# 40_PP1_PWR.net
KiCad netlist of a schematic drawn in Altium Designer
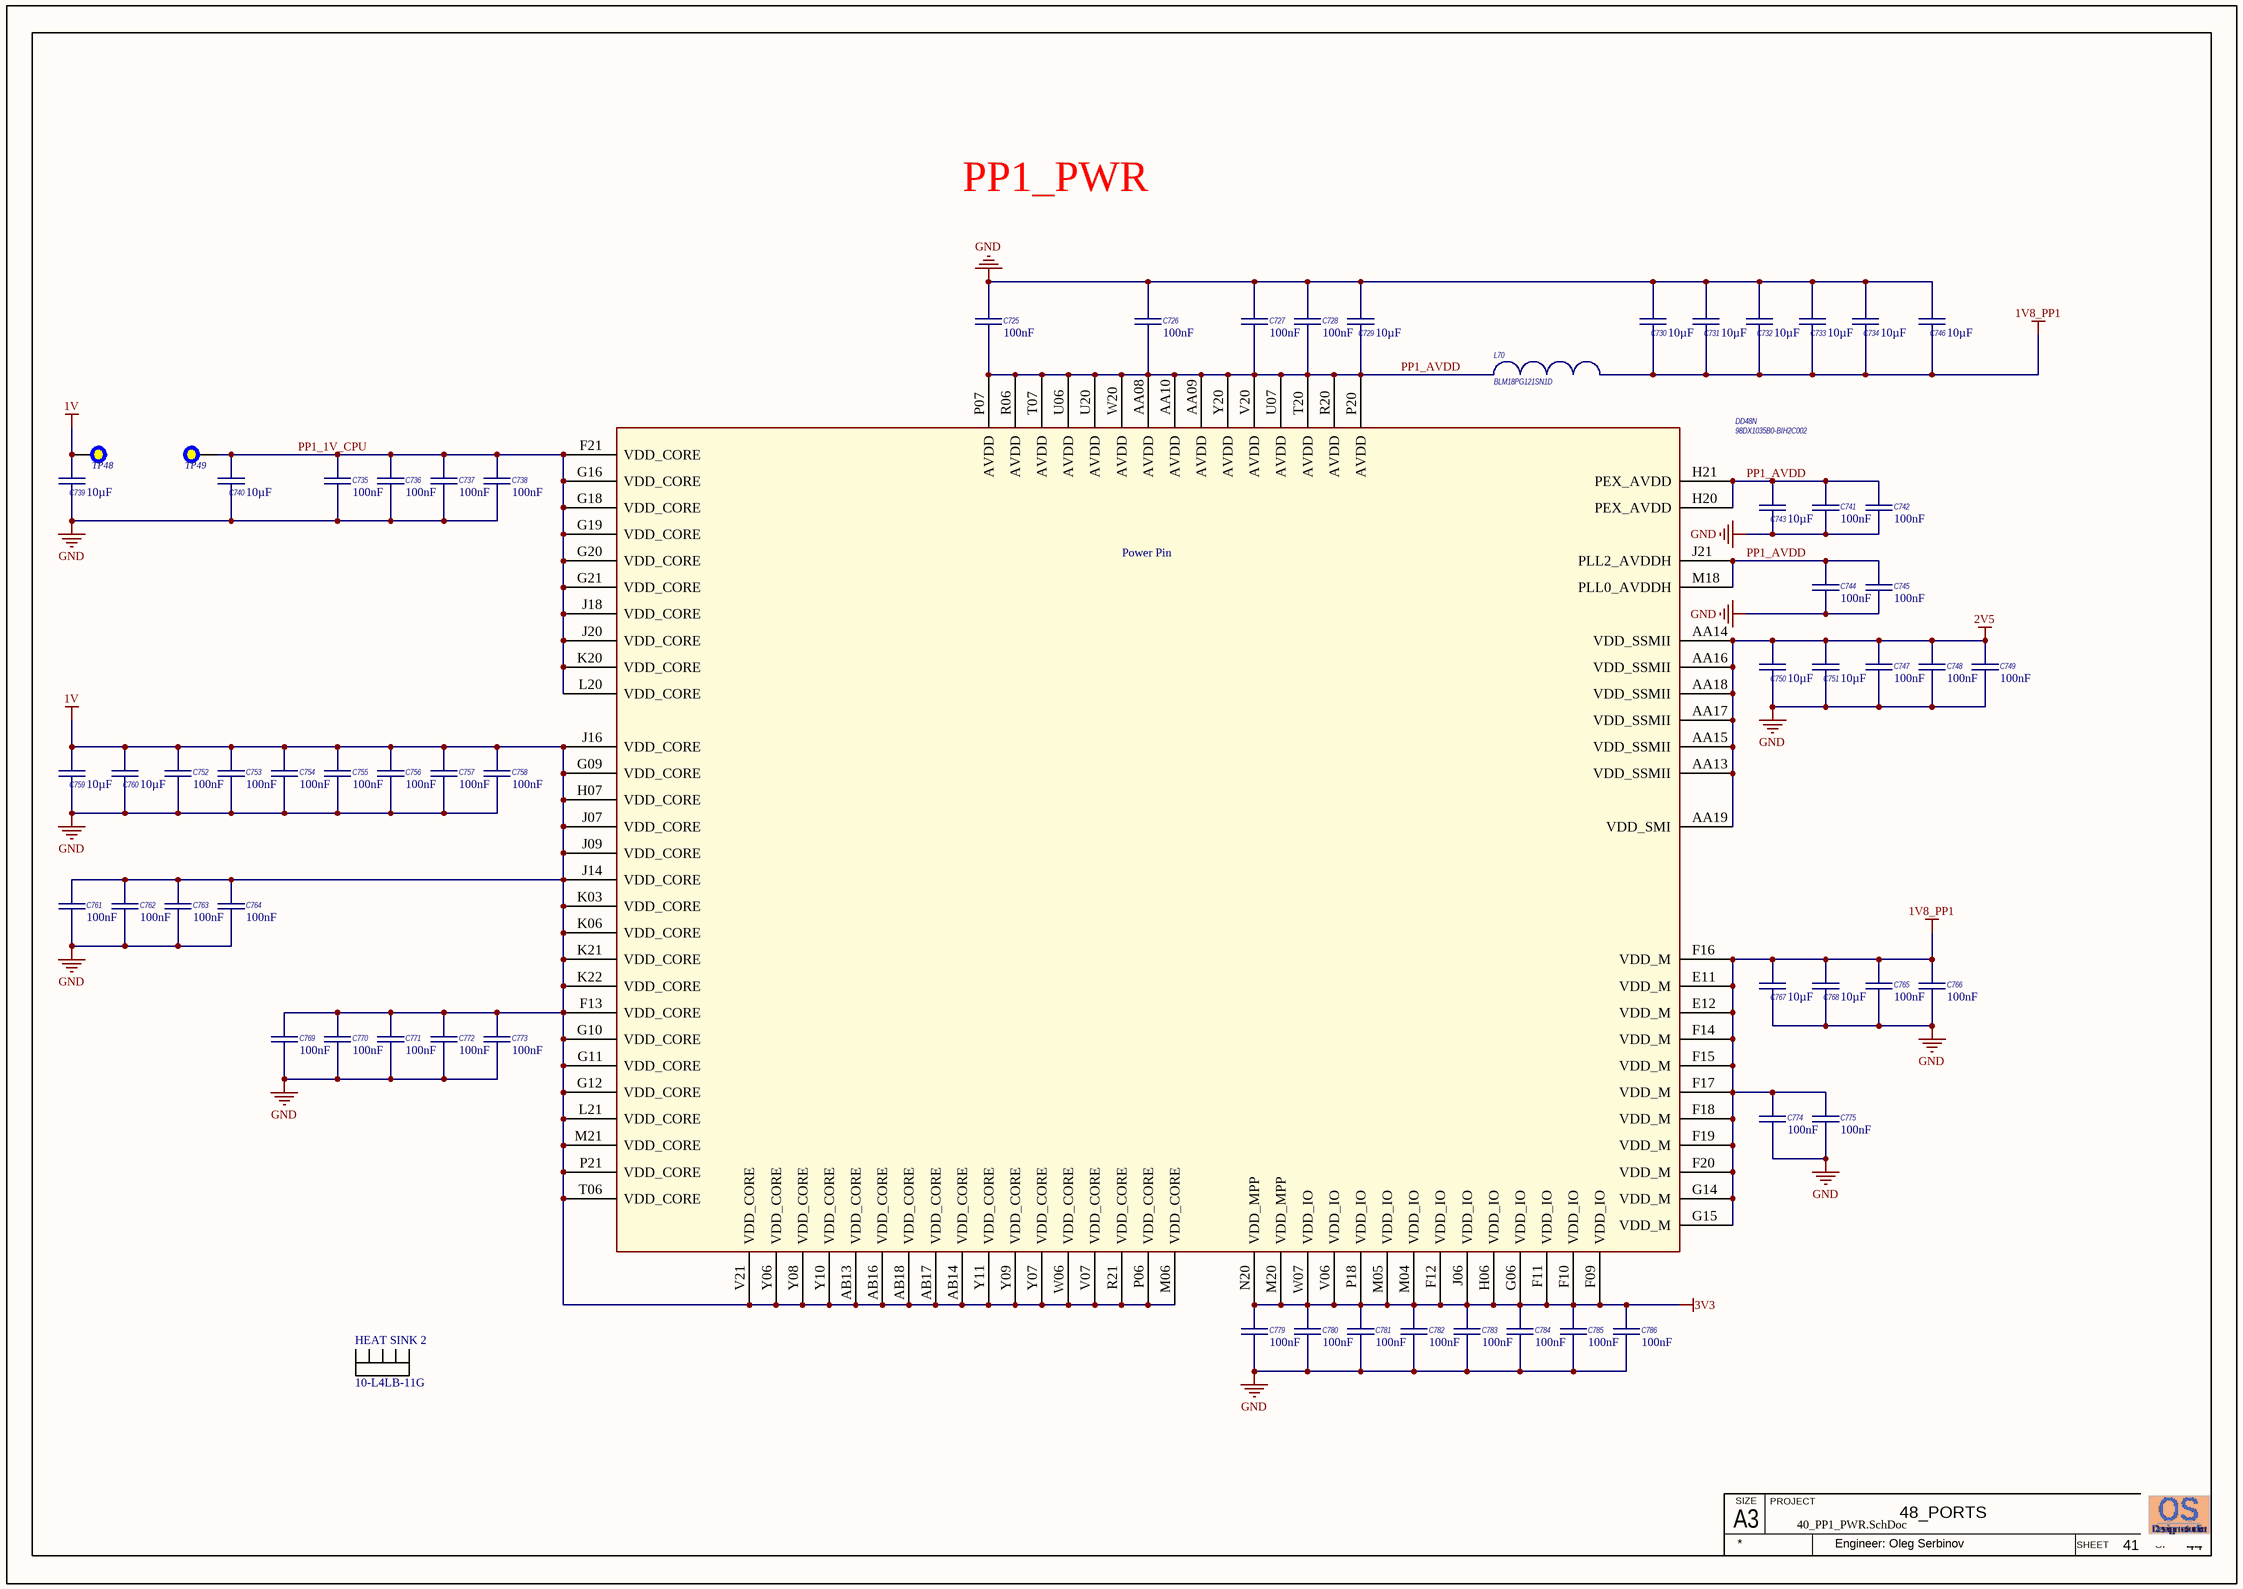
[diagram p0: 40_PP1_PWR.SchDoc]

(export (version "E")
  (design (tool "Eeschema 10.0.6"))
  (components
    (comp (ref "C725")
      (value "GRM155R71E104KE14D")
      (footprint "C0402_IPC High Density")
      (description "C0402, 100nF, 25V, X7R")
      (fields
        (field (name "MANUFACTURER") "Murata")
        (field (name "CAPACITANCE") "100nF")
        (field (name "CUSTOMER PART NUMBER") "Конденсатор, 100n, 0402, 25V, X7R, 10%")
      )
      (libsource (lib "CAPACITORS") (part "GRM155R71E104KE14D"))
    )
    (comp (ref "C726")
      (value "GRM155R71E104KE14D")
      (footprint "C0402_IPC High Density")
      (description "C0402, 100nF, 25V, X7R")
      (fields
        (field (name "MANUFACTURER") "Murata")
        (field (name "CAPACITANCE") "100nF")
        (field (name "CUSTOMER PART NUMBER") "Конденсатор, 100n, 0402, 25V, X7R, 10%")
      )
      (libsource (lib "CAPACITORS") (part "GRM155R71E104KE14D"))
    )
    (comp (ref "C727")
      (value "GRM155R71E104KE14D")
      (footprint "C0402_IPC High Density")
      (description "C0402, 100nF, 25V, X7R")
      (fields
        (field (name "MANUFACTURER") "Murata")
        (field (name "CAPACITANCE") "100nF")
        (field (name "CUSTOMER PART NUMBER") "Конденсатор, 100n, 0402, 25V, X7R, 10%")
      )
      (libsource (lib "CAPACITORS") (part "GRM155R71E104KE14D"))
    )
    (comp (ref "C728")
      (value "GRM155R71E104KE14D")
      (footprint "C0402_IPC High Density")
      (description "C0402, 100nF, 25V, X7R")
      (fields
        (field (name "MANUFACTURER") "Murata")
        (field (name "CAPACITANCE") "100nF")
        (field (name "CUSTOMER PART NUMBER") "Конденсатор, 100n, 0402, 25V, X7R, 10%")
      )
      (libsource (lib "CAPACITORS") (part "GRM155R71E104KE14D"))
    )
    (comp (ref "C729")
      (value "GRM21BR61C106KE15")
      (footprint "CAPC2012[0805]")
      (description "C0805, 10uF 10%, 16V, X5R")
      (fields
        (field (name "MANUFACTURER") "Murata")
        (field (name "TOLERANCE") "±10%")
        (field (name "CAPACITANCE") "10µF")
      )
      (libsource (lib "CAPACITORS") (part "GRM21BR61C106KE15"))
    )
    (comp (ref "C730")
      (value "GRM21BR61C106KE15")
      (footprint "CAPC2012[0805]")
      (description "C0805, 10uF 10%, 16V, X5R")
      (fields
        (field (name "MANUFACTURER") "Murata")
        (field (name "TOLERANCE") "±10%")
        (field (name "CAPACITANCE") "10µF")
      )
      (libsource (lib "CAPACITORS") (part "GRM21BR61C106KE15"))
    )
    (comp (ref "C731")
      (value "GRM21BR61C106KE15")
      (footprint "CAPC2012[0805]")
      (description "C0805, 10uF 10%, 16V, X5R")
      (fields
        (field (name "MANUFACTURER") "Murata")
        (field (name "TOLERANCE") "±10%")
        (field (name "CAPACITANCE") "10µF")
      )
      (libsource (lib "CAPACITORS") (part "GRM21BR61C106KE15"))
    )
    (comp (ref "C732")
      (value "GRM21BR61C106KE15")
      (footprint "CAPC2012[0805]")
      (description "C0805, 10uF 10%, 16V, X5R")
      (fields
        (field (name "MANUFACTURER") "Murata")
        (field (name "TOLERANCE") "±10%")
        (field (name "CAPACITANCE") "10µF")
      )
      (libsource (lib "CAPACITORS") (part "GRM21BR61C106KE15"))
    )
    (comp (ref "C733")
      (value "GRM21BR61C106KE15")
      (footprint "CAPC2012[0805]")
      (description "C0805, 10uF 10%, 16V, X5R")
      (fields
        (field (name "MANUFACTURER") "Murata")
        (field (name "TOLERANCE") "±10%")
        (field (name "CAPACITANCE") "10µF")
      )
      (libsource (lib "CAPACITORS") (part "GRM21BR61C106KE15"))
    )
    (comp (ref "C734")
      (value "GRM21BR61C106KE15")
      (footprint "CAPC2012[0805]")
      (description "C0805, 10uF 10%, 16V, X5R")
      (fields
        (field (name "MANUFACTURER") "Murata")
        (field (name "TOLERANCE") "±10%")
        (field (name "CAPACITANCE") "10µF")
      )
      (libsource (lib "CAPACITORS") (part "GRM21BR61C106KE15"))
    )
    (comp (ref "C735")
      (value "GRM155R71E104KE14D")
      (footprint "C0402_IPC High Density")
      (description "C0402, 100nF, 25V, X7R")
      (fields
        (field (name "MANUFACTURER") "Murata")
        (field (name "CAPACITANCE") "100nF")
        (field (name "CUSTOMER PART NUMBER") "Конденсатор, 100n, 0402, 25V, X7R, 10%")
      )
      (libsource (lib "CAPACITORS") (part "GRM155R71E104KE14D"))
    )
    (comp (ref "C736")
      (value "GRM155R71E104KE14D")
      (footprint "C0402_IPC High Density")
      (description "C0402, 100nF, 25V, X7R")
      (fields
        (field (name "MANUFACTURER") "Murata")
        (field (name "CAPACITANCE") "100nF")
        (field (name "CUSTOMER PART NUMBER") "Конденсатор, 100n, 0402, 25V, X7R, 10%")
      )
      (libsource (lib "CAPACITORS") (part "GRM155R71E104KE14D"))
    )
    (comp (ref "C737")
      (value "GRM155R71E104KE14D")
      (footprint "C0402_IPC High Density")
      (description "C0402, 100nF, 25V, X7R")
      (fields
        (field (name "MANUFACTURER") "Murata")
        (field (name "CAPACITANCE") "100nF")
        (field (name "CUSTOMER PART NUMBER") "Конденсатор, 100n, 0402, 25V, X7R, 10%")
      )
      (libsource (lib "CAPACITORS") (part "GRM155R71E104KE14D"))
    )
    (comp (ref "C738")
      (value "GRM155R71E104KE14D")
      (footprint "C0402_IPC High Density")
      (description "C0402, 100nF, 25V, X7R")
      (fields
        (field (name "MANUFACTURER") "Murata")
        (field (name "CAPACITANCE") "100nF")
        (field (name "CUSTOMER PART NUMBER") "Конденсатор, 100n, 0402, 25V, X7R, 10%")
      )
      (libsource (lib "CAPACITORS") (part "GRM155R71E104KE14D"))
    )
    (comp (ref "C739")
      (value "GRM21BR61C106KE15")
      (footprint "CAPC2012[0805]")
      (description "C0805, 10uF 10%, 16V, X5R")
      (fields
        (field (name "MANUFACTURER") "Murata")
        (field (name "TOLERANCE") "±10%")
        (field (name "CAPACITANCE") "10µF")
      )
      (libsource (lib "CAPACITORS") (part "GRM21BR61C106KE15"))
    )
    (comp (ref "C740")
      (value "GRM21BR61C106KE15")
      (footprint "CAPC2012[0805]")
      (description "C0805, 10uF 10%, 16V, X5R")
      (fields
        (field (name "MANUFACTURER") "Murata")
        (field (name "TOLERANCE") "±10%")
        (field (name "CAPACITANCE") "10µF")
      )
      (libsource (lib "CAPACITORS") (part "GRM21BR61C106KE15"))
    )
    (comp (ref "C741")
      (value "GRM155R71E104KE14D")
      (footprint "C0402_IPC High Density")
      (description "C0402, 100nF, 25V, X7R")
      (fields
        (field (name "MANUFACTURER") "Murata")
        (field (name "CAPACITANCE") "100nF")
        (field (name "CUSTOMER PART NUMBER") "Конденсатор, 100n, 0402, 25V, X7R, 10%")
      )
      (libsource (lib "CAPACITORS") (part "GRM155R71E104KE14D"))
    )
    (comp (ref "C742")
      (value "GRM155R71E104KE14D")
      (footprint "C0402_IPC High Density")
      (description "C0402, 100nF, 25V, X7R")
      (fields
        (field (name "MANUFACTURER") "Murata")
        (field (name "CAPACITANCE") "100nF")
        (field (name "CUSTOMER PART NUMBER") "Конденсатор, 100n, 0402, 25V, X7R, 10%")
      )
      (libsource (lib "CAPACITORS") (part "GRM155R71E104KE14D"))
    )
    (comp (ref "C743")
      (value "GRM21BR61C106KE15")
      (footprint "CAPC2012[0805]")
      (description "C0805, 10uF 10%, 16V, X5R")
      (fields
        (field (name "MANUFACTURER") "Murata")
        (field (name "TOLERANCE") "±10%")
        (field (name "CAPACITANCE") "10µF")
      )
      (libsource (lib "CAPACITORS") (part "GRM21BR61C106KE15"))
    )
    (comp (ref "C744")
      (value "GRM155R71E104KE14D")
      (footprint "C0402_IPC High Density")
      (description "C0402, 100nF, 25V, X7R")
      (fields
        (field (name "MANUFACTURER") "Murata")
        (field (name "CAPACITANCE") "100nF")
        (field (name "CUSTOMER PART NUMBER") "Конденсатор, 100n, 0402, 25V, X7R, 10%")
      )
      (libsource (lib "CAPACITORS") (part "GRM155R71E104KE14D"))
    )
    (comp (ref "C745")
      (value "GRM155R71E104KE14D")
      (footprint "C0402_IPC High Density")
      (description "C0402, 100nF, 25V, X7R")
      (fields
        (field (name "MANUFACTURER") "Murata")
        (field (name "CAPACITANCE") "100nF")
        (field (name "CUSTOMER PART NUMBER") "Конденсатор, 100n, 0402, 25V, X7R, 10%")
      )
      (libsource (lib "CAPACITORS") (part "GRM155R71E104KE14D"))
    )
    (comp (ref "C746")
      (value "GRM21BR61C106KE15")
      (footprint "CAPC2012[0805]")
      (description "C0805, 10uF 10%, 16V, X5R")
      (fields
        (field (name "MANUFACTURER") "Murata")
        (field (name "TOLERANCE") "±10%")
        (field (name "CAPACITANCE") "10µF")
      )
      (libsource (lib "CAPACITORS") (part "GRM21BR61C106KE15"))
    )
    (comp (ref "C747")
      (value "GRM155R71E104KE14D")
      (footprint "C0402_IPC High Density")
      (description "C0402, 100nF, 25V, X7R")
      (fields
        (field (name "MANUFACTURER") "Murata")
        (field (name "CAPACITANCE") "100nF")
        (field (name "CUSTOMER PART NUMBER") "Конденсатор, 100n, 0402, 25V, X7R, 10%")
      )
      (libsource (lib "CAPACITORS") (part "GRM155R71E104KE14D"))
    )
    (comp (ref "C748")
      (value "GRM155R71E104KE14D")
      (footprint "C0402_IPC High Density")
      (description "C0402, 100nF, 25V, X7R")
      (fields
        (field (name "MANUFACTURER") "Murata")
        (field (name "CAPACITANCE") "100nF")
        (field (name "CUSTOMER PART NUMBER") "Конденсатор, 100n, 0402, 25V, X7R, 10%")
      )
      (libsource (lib "CAPACITORS") (part "GRM155R71E104KE14D"))
    )
    (comp (ref "C749")
      (value "GRM155R71E104KE14D")
      (footprint "C0402_IPC High Density")
      (description "C0402, 100nF, 25V, X7R")
      (fields
        (field (name "MANUFACTURER") "Murata")
        (field (name "CAPACITANCE") "100nF")
        (field (name "CUSTOMER PART NUMBER") "Конденсатор, 100n, 0402, 25V, X7R, 10%")
      )
      (libsource (lib "CAPACITORS") (part "GRM155R71E104KE14D"))
    )
    (comp (ref "C750")
      (value "GRM21BR61C106KE15")
      (footprint "CAPC2012[0805]")
      (description "C0805, 10uF 10%, 16V, X5R")
      (fields
        (field (name "MANUFACTURER") "Murata")
        (field (name "TOLERANCE") "±10%")
        (field (name "CAPACITANCE") "10µF")
      )
      (libsource (lib "CAPACITORS") (part "GRM21BR61C106KE15"))
    )
    (comp (ref "C751")
      (value "GRM21BR61C106KE15")
      (footprint "CAPC2012[0805]")
      (description "C0805, 10uF 10%, 16V, X5R")
      (fields
        (field (name "MANUFACTURER") "Murata")
        (field (name "TOLERANCE") "±10%")
        (field (name "CAPACITANCE") "10µF")
      )
      (libsource (lib "CAPACITORS") (part "GRM21BR61C106KE15"))
    )
    (comp (ref "C752")
      (value "GRM155R71E104KE14D")
      (footprint "C0402_IPC High Density")
      (description "C0402, 100nF, 25V, X7R")
      (fields
        (field (name "MANUFACTURER") "Murata")
        (field (name "CAPACITANCE") "100nF")
        (field (name "CUSTOMER PART NUMBER") "Конденсатор, 100n, 0402, 25V, X7R, 10%")
      )
      (libsource (lib "CAPACITORS") (part "GRM155R71E104KE14D"))
    )
    (comp (ref "C753")
      (value "GRM155R71E104KE14D")
      (footprint "C0402_IPC High Density")
      (description "C0402, 100nF, 25V, X7R")
      (fields
        (field (name "MANUFACTURER") "Murata")
        (field (name "CAPACITANCE") "100nF")
        (field (name "CUSTOMER PART NUMBER") "Конденсатор, 100n, 0402, 25V, X7R, 10%")
      )
      (libsource (lib "CAPACITORS") (part "GRM155R71E104KE14D"))
    )
    (comp (ref "C754")
      (value "GRM155R71E104KE14D")
      (footprint "C0402_IPC High Density")
      (description "C0402, 100nF, 25V, X7R")
      (fields
        (field (name "MANUFACTURER") "Murata")
        (field (name "CAPACITANCE") "100nF")
        (field (name "CUSTOMER PART NUMBER") "Конденсатор, 100n, 0402, 25V, X7R, 10%")
      )
      (libsource (lib "CAPACITORS") (part "GRM155R71E104KE14D"))
    )
    (comp (ref "C755")
      (value "GRM155R71E104KE14D")
      (footprint "C0402_IPC High Density")
      (description "C0402, 100nF, 25V, X7R")
      (fields
        (field (name "MANUFACTURER") "Murata")
        (field (name "CAPACITANCE") "100nF")
        (field (name "CUSTOMER PART NUMBER") "Конденсатор, 100n, 0402, 25V, X7R, 10%")
      )
      (libsource (lib "CAPACITORS") (part "GRM155R71E104KE14D"))
    )
    (comp (ref "C756")
      (value "GRM155R71E104KE14D")
      (footprint "C0402_IPC High Density")
      (description "C0402, 100nF, 25V, X7R")
      (fields
        (field (name "MANUFACTURER") "Murata")
        (field (name "CAPACITANCE") "100nF")
        (field (name "CUSTOMER PART NUMBER") "Конденсатор, 100n, 0402, 25V, X7R, 10%")
      )
      (libsource (lib "CAPACITORS") (part "GRM155R71E104KE14D"))
    )
    (comp (ref "C757")
      (value "GRM155R71E104KE14D")
      (footprint "C0402_IPC High Density")
      (description "C0402, 100nF, 25V, X7R")
      (fields
        (field (name "MANUFACTURER") "Murata")
        (field (name "CAPACITANCE") "100nF")
        (field (name "CUSTOMER PART NUMBER") "Конденсатор, 100n, 0402, 25V, X7R, 10%")
      )
      (libsource (lib "CAPACITORS") (part "GRM155R71E104KE14D"))
    )
    (comp (ref "C758")
      (value "GRM155R71E104KE14D")
      (footprint "C0402_IPC High Density")
      (description "C0402, 100nF, 25V, X7R")
      (fields
        (field (name "MANUFACTURER") "Murata")
        (field (name "CAPACITANCE") "100nF")
        (field (name "CUSTOMER PART NUMBER") "Конденсатор, 100n, 0402, 25V, X7R, 10%")
      )
      (libsource (lib "CAPACITORS") (part "GRM155R71E104KE14D"))
    )
    (comp (ref "C759")
      (value "GRM21BR61C106KE15")
      (footprint "CAPC2012[0805]")
      (description "C0805, 10uF 10%, 16V, X5R")
      (fields
        (field (name "MANUFACTURER") "Murata")
        (field (name "TOLERANCE") "±10%")
        (field (name "CAPACITANCE") "10µF")
      )
      (libsource (lib "CAPACITORS") (part "GRM21BR61C106KE15"))
    )
    (comp (ref "C760")
      (value "GRM21BR61C106KE15")
      (footprint "CAPC2012[0805]")
      (description "C0805, 10uF 10%, 16V, X5R")
      (fields
        (field (name "MANUFACTURER") "Murata")
        (field (name "TOLERANCE") "±10%")
        (field (name "CAPACITANCE") "10µF")
      )
      (libsource (lib "CAPACITORS") (part "GRM21BR61C106KE15"))
    )
    (comp (ref "C761")
      (value "GRM155R71E104KE14D")
      (footprint "C0402_IPC High Density")
      (description "C0402, 100nF, 25V, X7R")
      (fields
        (field (name "MANUFACTURER") "Murata")
        (field (name "CAPACITANCE") "100nF")
        (field (name "CUSTOMER PART NUMBER") "Конденсатор, 100n, 0402, 25V, X7R, 10%")
      )
      (libsource (lib "CAPACITORS") (part "GRM155R71E104KE14D"))
    )
    (comp (ref "C762")
      (value "GRM155R71E104KE14D")
      (footprint "C0402_IPC High Density")
      (description "C0402, 100nF, 25V, X7R")
      (fields
        (field (name "MANUFACTURER") "Murata")
        (field (name "CAPACITANCE") "100nF")
        (field (name "CUSTOMER PART NUMBER") "Конденсатор, 100n, 0402, 25V, X7R, 10%")
      )
      (libsource (lib "CAPACITORS") (part "GRM155R71E104KE14D"))
    )
    (comp (ref "C763")
      (value "GRM155R71E104KE14D")
      (footprint "C0402_IPC High Density")
      (description "C0402, 100nF, 25V, X7R")
      (fields
        (field (name "MANUFACTURER") "Murata")
        (field (name "CAPACITANCE") "100nF")
        (field (name "CUSTOMER PART NUMBER") "Конденсатор, 100n, 0402, 25V, X7R, 10%")
      )
      (libsource (lib "CAPACITORS") (part "GRM155R71E104KE14D"))
    )
    (comp (ref "C764")
      (value "GRM155R71E104KE14D")
      (footprint "C0402_IPC High Density")
      (description "C0402, 100nF, 25V, X7R")
      (fields
        (field (name "MANUFACTURER") "Murata")
        (field (name "CAPACITANCE") "100nF")
        (field (name "CUSTOMER PART NUMBER") "Конденсатор, 100n, 0402, 25V, X7R, 10%")
      )
      (libsource (lib "CAPACITORS") (part "GRM155R71E104KE14D"))
    )
    (comp (ref "C765")
      (value "GRM155R71E104KE14D")
      (footprint "C0402_IPC High Density")
      (description "C0402, 100nF, 25V, X7R")
      (fields
        (field (name "MANUFACTURER") "Murata")
        (field (name "CAPACITANCE") "100nF")
        (field (name "CUSTOMER PART NUMBER") "Конденсатор, 100n, 0402, 25V, X7R, 10%")
      )
      (libsource (lib "CAPACITORS") (part "GRM155R71E104KE14D"))
    )
    (comp (ref "C766")
      (value "GRM155R71E104KE14D")
      (footprint "C0402_IPC High Density")
      (description "C0402, 100nF, 25V, X7R")
      (fields
        (field (name "MANUFACTURER") "Murata")
        (field (name "CAPACITANCE") "100nF")
        (field (name "CUSTOMER PART NUMBER") "Конденсатор, 100n, 0402, 25V, X7R, 10%")
      )
      (libsource (lib "CAPACITORS") (part "GRM155R71E104KE14D"))
    )
    (comp (ref "C767")
      (value "GRM21BR61C106KE15")
      (footprint "CAPC2012[0805]")
      (description "C0805, 10uF 10%, 16V, X5R")
      (fields
        (field (name "MANUFACTURER") "Murata")
        (field (name "TOLERANCE") "±10%")
        (field (name "CAPACITANCE") "10µF")
      )
      (libsource (lib "CAPACITORS") (part "GRM21BR61C106KE15"))
    )
    (comp (ref "C768")
      (value "GRM21BR61C106KE15")
      (footprint "CAPC2012[0805]")
      (description "C0805, 10uF 10%, 16V, X5R")
      (fields
        (field (name "MANUFACTURER") "Murata")
        (field (name "TOLERANCE") "±10%")
        (field (name "CAPACITANCE") "10µF")
      )
      (libsource (lib "CAPACITORS") (part "GRM21BR61C106KE15"))
    )
    (comp (ref "C769")
      (value "GRM155R71E104KE14D")
      (footprint "C0402_IPC High Density")
      (description "C0402, 100nF, 25V, X7R")
      (fields
        (field (name "MANUFACTURER") "Murata")
        (field (name "CAPACITANCE") "100nF")
        (field (name "CUSTOMER PART NUMBER") "Конденсатор, 100n, 0402, 25V, X7R, 10%")
      )
      (libsource (lib "CAPACITORS") (part "GRM155R71E104KE14D"))
    )
    (comp (ref "C770")
      (value "GRM155R71E104KE14D")
      (footprint "C0402_IPC High Density")
      (description "C0402, 100nF, 25V, X7R")
      (fields
        (field (name "MANUFACTURER") "Murata")
        (field (name "CAPACITANCE") "100nF")
        (field (name "CUSTOMER PART NUMBER") "Конденсатор, 100n, 0402, 25V, X7R, 10%")
      )
      (libsource (lib "CAPACITORS") (part "GRM155R71E104KE14D"))
    )
    (comp (ref "C771")
      (value "GRM155R71E104KE14D")
      (footprint "C0402_IPC High Density")
      (description "C0402, 100nF, 25V, X7R")
      (fields
        (field (name "MANUFACTURER") "Murata")
        (field (name "CAPACITANCE") "100nF")
        (field (name "CUSTOMER PART NUMBER") "Конденсатор, 100n, 0402, 25V, X7R, 10%")
      )
      (libsource (lib "CAPACITORS") (part "GRM155R71E104KE14D"))
    )
    (comp (ref "C772")
      (value "GRM155R71E104KE14D")
      (footprint "C0402_IPC High Density")
      (description "C0402, 100nF, 25V, X7R")
      (fields
        (field (name "MANUFACTURER") "Murata")
        (field (name "CAPACITANCE") "100nF")
        (field (name "CUSTOMER PART NUMBER") "Конденсатор, 100n, 0402, 25V, X7R, 10%")
      )
      (libsource (lib "CAPACITORS") (part "GRM155R71E104KE14D"))
    )
    (comp (ref "C773")
      (value "GRM155R71E104KE14D")
      (footprint "C0402_IPC High Density")
      (description "C0402, 100nF, 25V, X7R")
      (fields
        (field (name "MANUFACTURER") "Murata")
        (field (name "CAPACITANCE") "100nF")
        (field (name "CUSTOMER PART NUMBER") "Конденсатор, 100n, 0402, 25V, X7R, 10%")
      )
      (libsource (lib "CAPACITORS") (part "GRM155R71E104KE14D"))
    )
    (comp (ref "C774")
      (value "GRM155R71E104KE14D")
      (footprint "C0402_IPC High Density")
      (description "C0402, 100nF, 25V, X7R")
      (fields
        (field (name "MANUFACTURER") "Murata")
        (field (name "CAPACITANCE") "100nF")
        (field (name "CUSTOMER PART NUMBER") "Конденсатор, 100n, 0402, 25V, X7R, 10%")
      )
      (libsource (lib "CAPACITORS") (part "GRM155R71E104KE14D"))
    )
    (comp (ref "C775")
      (value "GRM155R71E104KE14D")
      (footprint "C0402_IPC High Density")
      (description "C0402, 100nF, 25V, X7R")
      (fields
        (field (name "MANUFACTURER") "Murata")
        (field (name "CAPACITANCE") "100nF")
        (field (name "CUSTOMER PART NUMBER") "Конденсатор, 100n, 0402, 25V, X7R, 10%")
      )
      (libsource (lib "CAPACITORS") (part "GRM155R71E104KE14D"))
    )
    (comp (ref "C779")
      (value "GRM155R71E104KE14D")
      (footprint "C0402_IPC High Density")
      (description "C0402, 100nF, 25V, X7R")
      (fields
        (field (name "MANUFACTURER") "Murata")
        (field (name "CAPACITANCE") "100nF")
        (field (name "CUSTOMER PART NUMBER") "Конденсатор, 100n, 0402, 25V, X7R, 10%")
      )
      (libsource (lib "CAPACITORS") (part "GRM155R71E104KE14D"))
    )
    (comp (ref "C780")
      (value "GRM155R71E104KE14D")
      (footprint "C0402_IPC High Density")
      (description "C0402, 100nF, 25V, X7R")
      (fields
        (field (name "MANUFACTURER") "Murata")
        (field (name "CAPACITANCE") "100nF")
        (field (name "CUSTOMER PART NUMBER") "Конденсатор, 100n, 0402, 25V, X7R, 10%")
      )
      (libsource (lib "CAPACITORS") (part "GRM155R71E104KE14D"))
    )
    (comp (ref "C781")
      (value "GRM155R71E104KE14D")
      (footprint "C0402_IPC High Density")
      (description "C0402, 100nF, 25V, X7R")
      (fields
        (field (name "MANUFACTURER") "Murata")
        (field (name "CAPACITANCE") "100nF")
        (field (name "CUSTOMER PART NUMBER") "Конденсатор, 100n, 0402, 25V, X7R, 10%")
      )
      (libsource (lib "CAPACITORS") (part "GRM155R71E104KE14D"))
    )
    (comp (ref "C782")
      (value "GRM155R71E104KE14D")
      (footprint "C0402_IPC High Density")
      (description "C0402, 100nF, 25V, X7R")
      (fields
        (field (name "MANUFACTURER") "Murata")
        (field (name "CAPACITANCE") "100nF")
        (field (name "CUSTOMER PART NUMBER") "Конденсатор, 100n, 0402, 25V, X7R, 10%")
      )
      (libsource (lib "CAPACITORS") (part "GRM155R71E104KE14D"))
    )
    (comp (ref "C783")
      (value "GRM155R71E104KE14D")
      (footprint "C0402_IPC High Density")
      (description "C0402, 100nF, 25V, X7R")
      (fields
        (field (name "MANUFACTURER") "Murata")
        (field (name "CAPACITANCE") "100nF")
        (field (name "CUSTOMER PART NUMBER") "Конденсатор, 100n, 0402, 25V, X7R, 10%")
      )
      (libsource (lib "CAPACITORS") (part "GRM155R71E104KE14D"))
    )
    (comp (ref "C784")
      (value "GRM155R71E104KE14D")
      (footprint "C0402_IPC High Density")
      (description "C0402, 100nF, 25V, X7R")
      (fields
        (field (name "MANUFACTURER") "Murata")
        (field (name "CAPACITANCE") "100nF")
        (field (name "CUSTOMER PART NUMBER") "Конденсатор, 100n, 0402, 25V, X7R, 10%")
      )
      (libsource (lib "CAPACITORS") (part "GRM155R71E104KE14D"))
    )
    (comp (ref "C785")
      (value "GRM155R71E104KE14D")
      (footprint "C0402_IPC High Density")
      (description "C0402, 100nF, 25V, X7R")
      (fields
        (field (name "MANUFACTURER") "Murata")
        (field (name "CAPACITANCE") "100nF")
        (field (name "CUSTOMER PART NUMBER") "Конденсатор, 100n, 0402, 25V, X7R, 10%")
      )
      (libsource (lib "CAPACITORS") (part "GRM155R71E104KE14D"))
    )
    (comp (ref "C786")
      (value "GRM155R71E104KE14D")
      (footprint "C0402_IPC High Density")
      (description "C0402, 100nF, 25V, X7R")
      (fields
        (field (name "MANUFACTURER") "Murata")
        (field (name "CAPACITANCE") "100nF")
        (field (name "CUSTOMER PART NUMBER") "Конденсатор, 100n, 0402, 25V, X7R, 10%")
      )
      (libsource (lib "CAPACITORS") (part "GRM155R71E104KE14D"))
    )
    (comp (ref "DD48")
      (value "98DX1035B0-BIH2C002")
      (footprint "HSBGA617_27X27_1MM")
      (description "IC 24-PORT FE  4-PORT 2.5GE L2 ENTRY-LEVEL, CPU")
      (fields
        (field (name "CUSTOMER PART NUMBER") "Микросхема, 98DX1035B0-BIH2C002, IC 24-PORT FE 4-PORT 2.5GE L2 ENTRY-LEVEL, HSBGA617SBGA617")
        (field (name "MANUFACTURER") "Marvell Technology Group")
      )
      (libsource (lib "DIGITAL and ANALIG ICs") (part "98DX1035A1-BIH2C002"))
    )
    (comp (ref "HEAT SINK 2")
      (value "10-L4LB-11G")
      (footprint "10-L4LB-11G")
      (description "HEAT SINK  45.2x41.4")
      (fields
        (field (name "MANUFACTURER") "Aavid Thermalloy")
        (field (name "CUSTOMER PART NUMBER") "Радиатор, 10-L4LB-11G, Pin Fin heat sink with Push Pin attachment")
      )
      (libsource (lib "HEAT SINK") (part "10-L4LB-11G"))
    )
    (comp (ref "L70")
      (value "BLM18PG121SN1D")
      (footprint "INDC1608X95N")
      (description "FILTER BLM18 (0603, 2A)")
      (fields
        (field (name "MANUFACTURER") "Murata")
        (field (name "RPART NUMBER") "MPZ1608S121ATAH0 ; CIC10P121NC ; MPZ1608S121ATDH5 ; BLM18PG121SH1D ; 742792625")
      )
      (libsource (lib "INDUCTORS") (part "BLM18PG121SN1D"))
    )
    (comp (ref "TP48")
      (value "Test Point 0.5mm pad")
      (footprint "Test Point 0.5mm")
      (libsource (lib "CONNECTORS") (part "Test Point 0.5mm pad"))
    )
    (comp (ref "TP49")
      (value "Test Point 0.5mm pad")
      (footprint "Test Point 0.5mm")
      (libsource (lib "CONNECTORS") (part "Test Point 0.5mm pad"))
    )
  )
  (nets
    (net (code "1") (name "/PP1_1V_CPU") (class "Default")
      (node (ref "C735") (pin "1") (pintype "passive"))
      (node (ref "C736") (pin "1") (pintype "passive"))
      (node (ref "C737") (pin "1") (pintype "passive"))
      (node (ref "C738") (pin "1") (pintype "passive"))
      (node (ref "C740") (pin "2") (pintype "passive"))
      (node (ref "DD48") (pin "F21") (pinfunction "VDD_CORE_F21") (pintype "power_in"))
      (node (ref "DD48") (pin "G16") (pinfunction "VDD_CORE_G16") (pintype "power_in"))
      (node (ref "DD48") (pin "G18") (pinfunction "VDD_CORE_G18") (pintype "power_in"))
      (node (ref "DD48") (pin "G19") (pinfunction "VDD_CORE_G19") (pintype "power_in"))
      (node (ref "DD48") (pin "G20") (pinfunction "VDD_CORE_G20") (pintype "power_in"))
      (node (ref "DD48") (pin "G21") (pinfunction "VDD_CORE_G21") (pintype "power_in"))
      (node (ref "DD48") (pin "J18") (pinfunction "VDD_CORE_J18") (pintype "power_in"))
      (node (ref "DD48") (pin "J20") (pinfunction "VDD_CORE_J20") (pintype "power_in"))
      (node (ref "DD48") (pin "K20") (pinfunction "VDD_CORE_K20") (pintype "power_in"))
      (node (ref "DD48") (pin "L20") (pinfunction "VDD_CORE_L20") (pintype "power_in"))
      (node (ref "TP49") (pin "1") (pinfunction "1_1") (pintype "passive"))
    )
    (net (code "2") (name "/PP1_AVDD") (class "Default")
      (node (ref "C725") (pin "2") (pintype "passive"))
      (node (ref "C726") (pin "2") (pintype "passive"))
      (node (ref "C727") (pin "2") (pintype "passive"))
      (node (ref "C728") (pin "2") (pintype "passive"))
      (node (ref "C729") (pin "1") (pintype "passive"))
      (node (ref "C741") (pin "1") (pintype "passive"))
      (node (ref "C742") (pin "1") (pintype "passive"))
      (node (ref "C743") (pin "2") (pintype "passive"))
      (node (ref "C744") (pin "1") (pintype "passive"))
      (node (ref "C745") (pin "1") (pintype "passive"))
      (node (ref "DD48") (pin "AA08") (pinfunction "AVDD_AA08") (pintype "power_in"))
      (node (ref "DD48") (pin "AA09") (pinfunction "AVDD_AA09") (pintype "power_in"))
      (node (ref "DD48") (pin "AA10") (pinfunction "AVDD_AA10") (pintype "power_in"))
      (node (ref "DD48") (pin "H20") (pinfunction "PEX_AVDD_H20") (pintype "power_in"))
      (node (ref "DD48") (pin "H21") (pinfunction "PEX_AVDD_H21") (pintype "power_in"))
      (node (ref "DD48") (pin "J21") (pinfunction "PLL2_AVDDH_J21") (pintype "power_in"))
      (node (ref "DD48") (pin "M18") (pinfunction "PLL0_AVDDH_M18") (pintype "power_in"))
      (node (ref "DD48") (pin "P07") (pinfunction "AVDD_P07") (pintype "power_in"))
      (node (ref "DD48") (pin "P20") (pinfunction "AVDD_P20") (pintype "power_in"))
      (node (ref "DD48") (pin "R06") (pinfunction "AVDD_R06") (pintype "power_in"))
      (node (ref "DD48") (pin "R20") (pinfunction "AVDD_R20") (pintype "power_in"))
      (node (ref "DD48") (pin "T07") (pinfunction "AVDD_T07") (pintype "power_in"))
      (node (ref "DD48") (pin "T20") (pinfunction "AVDD_T20") (pintype "power_in"))
      (node (ref "DD48") (pin "U06") (pinfunction "AVDD_U06") (pintype "power_in"))
      (node (ref "DD48") (pin "U07") (pinfunction "AVDD_U07") (pintype "power_in"))
      (node (ref "DD48") (pin "U20") (pinfunction "AVDD_U20") (pintype "power_in"))
      (node (ref "DD48") (pin "V20") (pinfunction "AVDD_V20") (pintype "power_in"))
      (node (ref "DD48") (pin "W20") (pinfunction "AVDD_W20") (pintype "power_in"))
      (node (ref "DD48") (pin "Y20") (pinfunction "AVDD_Y20") (pintype "power_in"))
      (node (ref "L70") (pin "1") (pinfunction "1_1") (pintype "passive"))
    )
    (net (code "3") (name "1V") (class "Default")
      (node (ref "C739") (pin "2") (pintype "passive"))
      (node (ref "C752") (pin "1") (pintype "passive"))
      (node (ref "C753") (pin "1") (pintype "passive"))
      (node (ref "C754") (pin "1") (pintype "passive"))
      (node (ref "C755") (pin "1") (pintype "passive"))
      (node (ref "C756") (pin "1") (pintype "passive"))
      (node (ref "C757") (pin "1") (pintype "passive"))
      (node (ref "C758") (pin "1") (pintype "passive"))
      (node (ref "C759") (pin "2") (pintype "passive"))
      (node (ref "C760") (pin "2") (pintype "passive"))
      (node (ref "C761") (pin "1") (pintype "passive"))
      (node (ref "C762") (pin "1") (pintype "passive"))
      (node (ref "C763") (pin "1") (pintype "passive"))
      (node (ref "C764") (pin "1") (pintype "passive"))
      (node (ref "C769") (pin "1") (pintype "passive"))
      (node (ref "C770") (pin "1") (pintype "passive"))
      (node (ref "C771") (pin "1") (pintype "passive"))
      (node (ref "C772") (pin "1") (pintype "passive"))
      (node (ref "C773") (pin "1") (pintype "passive"))
      (node (ref "DD48") (pin "AB13") (pinfunction "VDD_CORE_AB13") (pintype "power_in"))
      (node (ref "DD48") (pin "AB14") (pinfunction "VDD_CORE_AB14") (pintype "power_in"))
      (node (ref "DD48") (pin "AB16") (pinfunction "VDD_CORE_AB16") (pintype "power_in"))
      (node (ref "DD48") (pin "AB17") (pinfunction "VDD_CORE_AB17") (pintype "power_in"))
      (node (ref "DD48") (pin "AB18") (pinfunction "VDD_CORE_AB18") (pintype "power_in"))
      (node (ref "DD48") (pin "F13") (pinfunction "VDD_CORE_F13") (pintype "power_in"))
      (node (ref "DD48") (pin "G09") (pinfunction "VDD_CORE_G09") (pintype "power_in"))
      (node (ref "DD48") (pin "G10") (pinfunction "VDD_CORE_G10") (pintype "power_in"))
      (node (ref "DD48") (pin "G11") (pinfunction "VDD_CORE_G11") (pintype "power_in"))
      (node (ref "DD48") (pin "G12") (pinfunction "VDD_CORE_G12") (pintype "power_in"))
      (node (ref "DD48") (pin "H07") (pinfunction "VDD_CORE_H07") (pintype "power_in"))
      (node (ref "DD48") (pin "J07") (pinfunction "VDD_CORE_J07") (pintype "power_in"))
      (node (ref "DD48") (pin "J09") (pinfunction "VDD_CORE_J09") (pintype "power_in"))
      (node (ref "DD48") (pin "J14") (pinfunction "VDD_CORE_J14") (pintype "power_in"))
      (node (ref "DD48") (pin "J16") (pinfunction "VDD_CORE_J16") (pintype "power_in"))
      (node (ref "DD48") (pin "K03") (pinfunction "VDD_CORE_K03") (pintype "power_in"))
      (node (ref "DD48") (pin "K06") (pinfunction "VDD_CORE_K06") (pintype "power_in"))
      (node (ref "DD48") (pin "K21") (pinfunction "VDD_CORE_K21") (pintype "power_in"))
      (node (ref "DD48") (pin "K22") (pinfunction "VDD_CORE_K22") (pintype "power_in"))
      (node (ref "DD48") (pin "L21") (pinfunction "VDD_CORE_L21") (pintype "power_in"))
      (node (ref "DD48") (pin "M06") (pinfunction "VDD_CORE_M06") (pintype "power_in"))
      (node (ref "DD48") (pin "M21") (pinfunction "VDD_CORE_M21") (pintype "power_in"))
      (node (ref "DD48") (pin "P06") (pinfunction "VDD_CORE_P06") (pintype "power_in"))
      (node (ref "DD48") (pin "P21") (pinfunction "VDD_CORE_P21") (pintype "power_in"))
      (node (ref "DD48") (pin "R21") (pinfunction "VDD_CORE_R21") (pintype "power_in"))
      (node (ref "DD48") (pin "T06") (pinfunction "VDD_CORE_T06") (pintype "power_in"))
      (node (ref "DD48") (pin "V07") (pinfunction "VDD_CORE_V07") (pintype "power_in"))
      (node (ref "DD48") (pin "V21") (pinfunction "VDD_CORE_V21") (pintype "power_in"))
      (node (ref "DD48") (pin "W06") (pinfunction "VDD_CORE_W06") (pintype "power_in"))
      (node (ref "DD48") (pin "Y06") (pinfunction "VDD_CORE_Y06") (pintype "power_in"))
      (node (ref "DD48") (pin "Y07") (pinfunction "VDD_CORE_Y07") (pintype "power_in"))
      (node (ref "DD48") (pin "Y08") (pinfunction "VDD_CORE_Y08") (pintype "power_in"))
      (node (ref "DD48") (pin "Y09") (pinfunction "VDD_CORE_Y09") (pintype "power_in"))
      (node (ref "DD48") (pin "Y10") (pinfunction "VDD_CORE_Y10") (pintype "power_in"))
      (node (ref "DD48") (pin "Y11") (pinfunction "VDD_CORE_Y11") (pintype "power_in"))
      (node (ref "TP48") (pin "1") (pinfunction "1_1") (pintype "passive"))
    )
    (net (code "4") (name "1V8_PP1") (class "Default")
      (node (ref "C730") (pin "1") (pintype "passive"))
      (node (ref "C731") (pin "1") (pintype "passive"))
      (node (ref "C732") (pin "1") (pintype "passive"))
      (node (ref "C733") (pin "1") (pintype "passive"))
      (node (ref "C734") (pin "1") (pintype "passive"))
      (node (ref "C746") (pin "1") (pintype "passive"))
      (node (ref "C765") (pin "1") (pintype "passive"))
      (node (ref "C766") (pin "1") (pintype "passive"))
      (node (ref "C767") (pin "2") (pintype "passive"))
      (node (ref "C768") (pin "2") (pintype "passive"))
      (node (ref "C774") (pin "1") (pintype "passive"))
      (node (ref "C775") (pin "1") (pintype "passive"))
      (node (ref "DD48") (pin "E11") (pinfunction "VDD_M_E11") (pintype "power_in"))
      (node (ref "DD48") (pin "E12") (pinfunction "VDD_M_E12") (pintype "power_in"))
      (node (ref "DD48") (pin "F14") (pinfunction "VDD_M_F14") (pintype "power_in"))
      (node (ref "DD48") (pin "F15") (pinfunction "VDD_M_F15") (pintype "power_in"))
      (node (ref "DD48") (pin "F16") (pinfunction "VDD_M_F16") (pintype "power_in"))
      (node (ref "DD48") (pin "F17") (pinfunction "VDD_M_F17") (pintype "power_in"))
      (node (ref "DD48") (pin "F18") (pinfunction "VDD_M_F18") (pintype "power_in"))
      (node (ref "DD48") (pin "F19") (pinfunction "VDD_M_F19") (pintype "power_in"))
      (node (ref "DD48") (pin "F20") (pinfunction "VDD_M_F20") (pintype "power_in"))
      (node (ref "DD48") (pin "G14") (pinfunction "VDD_M_G14") (pintype "power_in"))
      (node (ref "DD48") (pin "G15") (pinfunction "VDD_M_G15") (pintype "power_in"))
      (node (ref "L70") (pin "2") (pinfunction "2_2") (pintype "passive"))
    )
    (net (code "5") (name "2V5") (class "Default")
      (node (ref "C747") (pin "1") (pintype "passive"))
      (node (ref "C748") (pin "1") (pintype "passive"))
      (node (ref "C749") (pin "1") (pintype "passive"))
      (node (ref "C750") (pin "2") (pintype "passive"))
      (node (ref "C751") (pin "2") (pintype "passive"))
      (node (ref "DD48") (pin "AA13") (pinfunction "VDD_SSMII_AA13") (pintype "power_in"))
      (node (ref "DD48") (pin "AA14") (pinfunction "VDD_SSMII_AA14") (pintype "power_in"))
      (node (ref "DD48") (pin "AA15") (pinfunction "VDD_SSMII_AA15") (pintype "power_in"))
      (node (ref "DD48") (pin "AA16") (pinfunction "VDD_SSMII_AA16") (pintype "power_in"))
      (node (ref "DD48") (pin "AA17") (pinfunction "VDD_SSMII_AA17") (pintype "power_in"))
      (node (ref "DD48") (pin "AA18") (pinfunction "VDD_SSMII_AA18") (pintype "power_in"))
      (node (ref "DD48") (pin "AA19") (pinfunction "VDD_SMI_AA19") (pintype "power_in"))
    )
    (net (code "6") (name "3V3") (class "Default")
      (node (ref "C779") (pin "1") (pintype "passive"))
      (node (ref "C780") (pin "1") (pintype "passive"))
      (node (ref "C781") (pin "1") (pintype "passive"))
      (node (ref "C782") (pin "1") (pintype "passive"))
      (node (ref "C783") (pin "1") (pintype "passive"))
      (node (ref "C784") (pin "1") (pintype "passive"))
      (node (ref "C785") (pin "1") (pintype "passive"))
      (node (ref "C786") (pin "1") (pintype "passive"))
      (node (ref "DD48") (pin "F09") (pinfunction "VDD_IO_F09") (pintype "power_in"))
      (node (ref "DD48") (pin "F10") (pinfunction "VDD_IO_F10") (pintype "power_in"))
      (node (ref "DD48") (pin "F11") (pinfunction "VDD_IO_F11") (pintype "power_in"))
      (node (ref "DD48") (pin "F12") (pinfunction "VDD_IO_F12") (pintype "power_in"))
      (node (ref "DD48") (pin "G06") (pinfunction "VDD_IO_G06") (pintype "power_in"))
      (node (ref "DD48") (pin "H06") (pinfunction "VDD_IO_H06") (pintype "power_in"))
      (node (ref "DD48") (pin "J06") (pinfunction "VDD_IO_J06") (pintype "power_in"))
      (node (ref "DD48") (pin "M04") (pinfunction "VDD_IO_M04") (pintype "power_in"))
      (node (ref "DD48") (pin "M05") (pinfunction "VDD_IO_M05") (pintype "power_in"))
      (node (ref "DD48") (pin "M20") (pinfunction "VDD_MPP_M20") (pintype "power_in"))
      (node (ref "DD48") (pin "N20") (pinfunction "VDD_MPP_N20") (pintype "power_in"))
      (node (ref "DD48") (pin "P18") (pinfunction "VDD_IO_P18") (pintype "power_in"))
      (node (ref "DD48") (pin "V06") (pinfunction "VDD_IO_V06") (pintype "power_in"))
      (node (ref "DD48") (pin "W07") (pinfunction "VDD_IO_W07") (pintype "power_in"))
    )
    (net (code "7") (name "GND") (class "Default")
      (node (ref "C725") (pin "1") (pintype "passive"))
      (node (ref "C726") (pin "1") (pintype "passive"))
      (node (ref "C727") (pin "1") (pintype "passive"))
      (node (ref "C728") (pin "1") (pintype "passive"))
      (node (ref "C729") (pin "2") (pintype "passive"))
      (node (ref "C730") (pin "2") (pintype "passive"))
      (node (ref "C731") (pin "2") (pintype "passive"))
      (node (ref "C732") (pin "2") (pintype "passive"))
      (node (ref "C733") (pin "2") (pintype "passive"))
      (node (ref "C734") (pin "2") (pintype "passive"))
      (node (ref "C735") (pin "2") (pintype "passive"))
      (node (ref "C736") (pin "2") (pintype "passive"))
      (node (ref "C737") (pin "2") (pintype "passive"))
      (node (ref "C738") (pin "2") (pintype "passive"))
      (node (ref "C739") (pin "1") (pintype "passive"))
      (node (ref "C740") (pin "1") (pintype "passive"))
      (node (ref "C741") (pin "2") (pintype "passive"))
      (node (ref "C742") (pin "2") (pintype "passive"))
      (node (ref "C743") (pin "1") (pintype "passive"))
      (node (ref "C744") (pin "2") (pintype "passive"))
      (node (ref "C745") (pin "2") (pintype "passive"))
      (node (ref "C746") (pin "2") (pintype "passive"))
      (node (ref "C747") (pin "2") (pintype "passive"))
      (node (ref "C748") (pin "2") (pintype "passive"))
      (node (ref "C749") (pin "2") (pintype "passive"))
      (node (ref "C750") (pin "1") (pintype "passive"))
      (node (ref "C751") (pin "1") (pintype "passive"))
      (node (ref "C752") (pin "2") (pintype "passive"))
      (node (ref "C753") (pin "2") (pintype "passive"))
      (node (ref "C754") (pin "2") (pintype "passive"))
      (node (ref "C755") (pin "2") (pintype "passive"))
      (node (ref "C756") (pin "2") (pintype "passive"))
      (node (ref "C757") (pin "2") (pintype "passive"))
      (node (ref "C758") (pin "2") (pintype "passive"))
      (node (ref "C759") (pin "1") (pintype "passive"))
      (node (ref "C760") (pin "1") (pintype "passive"))
      (node (ref "C761") (pin "2") (pintype "passive"))
      (node (ref "C762") (pin "2") (pintype "passive"))
      (node (ref "C763") (pin "2") (pintype "passive"))
      (node (ref "C764") (pin "2") (pintype "passive"))
      (node (ref "C765") (pin "2") (pintype "passive"))
      (node (ref "C766") (pin "2") (pintype "passive"))
      (node (ref "C767") (pin "1") (pintype "passive"))
      (node (ref "C768") (pin "1") (pintype "passive"))
      (node (ref "C769") (pin "2") (pintype "passive"))
      (node (ref "C770") (pin "2") (pintype "passive"))
      (node (ref "C771") (pin "2") (pintype "passive"))
      (node (ref "C772") (pin "2") (pintype "passive"))
      (node (ref "C773") (pin "2") (pintype "passive"))
      (node (ref "C774") (pin "2") (pintype "passive"))
      (node (ref "C775") (pin "2") (pintype "passive"))
      (node (ref "C779") (pin "2") (pintype "passive"))
      (node (ref "C780") (pin "2") (pintype "passive"))
      (node (ref "C781") (pin "2") (pintype "passive"))
      (node (ref "C782") (pin "2") (pintype "passive"))
      (node (ref "C783") (pin "2") (pintype "passive"))
      (node (ref "C784") (pin "2") (pintype "passive"))
      (node (ref "C785") (pin "2") (pintype "passive"))
      (node (ref "C786") (pin "2") (pintype "passive"))
    )
  )
)
